# cs301_Team01_Schematic_Sensor.net
KiCad netlist of a schematic drawn in Altium Designer
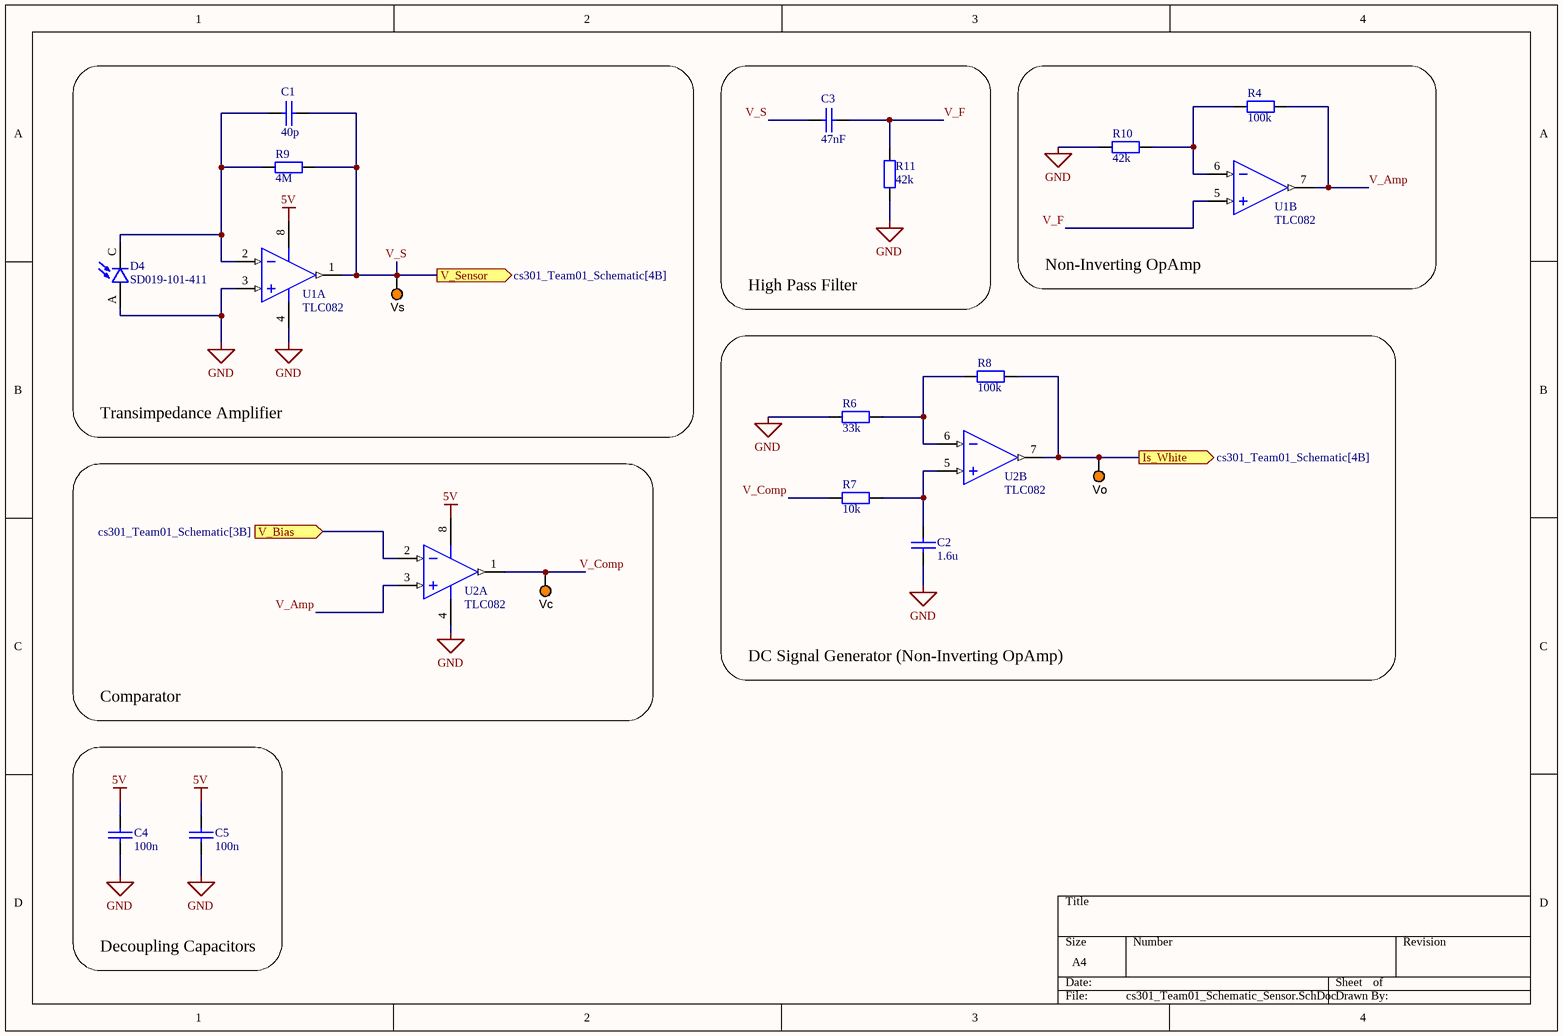
[diagram p0: cs301_Team01_Schematic_Sensor.SchDoc]

(export (version "E")
  (design (tool "Eeschema 10.0.6"))
  (components
    (comp (ref "C1")
      (value "40p")
      (footprint "0805 CAP")
      (description "SMT ceramic capacitor 0805 size")
      (libsource (lib "EE209_Library") (part "CerCap_SMT_0805"))
    )
    (comp (ref "C2")
      (value "1.6u")
      (footprint "0805 CAP")
      (description "SMT ceramic capacitor 0805 size")
      (libsource (lib "EE209_Library") (part "CerCap_SMT_0805"))
    )
    (comp (ref "C3")
      (value "47nF")
      (footprint "0805 CAP")
      (description "SMT ceramic capacitor 0805 size")
      (libsource (lib "EE209_Library") (part "CerCap_SMT_0805"))
    )
    (comp (ref "C4")
      (value "100n")
      (footprint "0805 CAP")
      (description "SMT ceramic capacitor 0805 size")
      (libsource (lib "EE209_Library") (part "CerCap_SMT_0805"))
    )
    (comp (ref "C5")
      (value "100n")
      (footprint "0805 CAP")
      (description "SMT ceramic capacitor 0805 size")
      (libsource (lib "EE209_Library") (part "CerCap_SMT_0805"))
    )
    (comp (ref "D4")
      (value "SD019-101-411")
      (footprint "XDCR_TEMD7000X01")
      (description "Photodiode SD019-101-411")
      (fields (field (name "MF") "Vishay Semiconductor") (field (name "MP") "TEMD7000X01"))
      (libsource (lib "TEMD7000X01") (part "TEMD7000X01"))
    )
    (comp (ref "R4")
      (value "100k")
      (footprint "0805 RES")
      (description "0805 resistor")
      (fields (field (name "PUBLISHER") "Altium Limited"))
      (libsource (lib "") (part "Res_SMT_0805_2"))
    )
    (comp (ref "R6")
      (value "33k")
      (footprint "0805 RES")
      (description "0805 resistor")
      (fields (field (name "PUBLISHER") "Altium Limited"))
      (libsource (lib "") (part "Res_SMT_0805_1"))
    )
    (comp (ref "R7")
      (value "10k")
      (footprint "0805 RES")
      (description "0805 resistor")
      (fields (field (name "PUBLISHER") "Altium Limited"))
      (libsource (lib "") (part "Res_SMT_0805_1"))
    )
    (comp (ref "R8")
      (value "100k")
      (footprint "0805 RES")
      (description "0805 resistor")
      (fields (field (name "PUBLISHER") "Altium Limited"))
      (libsource (lib "") (part "Res_SMT_0805_1"))
    )
    (comp (ref "R9")
      (value "4M")
      (footprint "0805 RES")
      (description "0805 resistor")
      (fields (field (name "PUBLISHER") "Altium Limited"))
      (libsource (lib "") (part "Res_SMT_0805_2"))
    )
    (comp (ref "R10")
      (value "42k")
      (footprint "0805 RES")
      (description "0805 resistor")
      (fields (field (name "PUBLISHER") "Altium Limited"))
      (libsource (lib "") (part "Res_SMT_0805_2"))
    )
    (comp (ref "R11")
      (value "42k")
      (footprint "0805 RES")
      (description "0805 resistor")
      (fields (field (name "PUBLISHER") "Altium Limited"))
      (libsource (lib "EE209_Library") (part "Res_SMT_0805"))
    )
    (comp (ref "U1")
      (value "TLC082")
      (footprint "SO - 8")
      (description "IC OPAMP GP 10MHZ 8SOIC")
      (fields
        (field (name "MANUFACTURER") "Texas Instruments")
        (field (name "MANUFACTURER PART NUMBER") "TLC082CDR")
      )
      (libsource (lib "EE209_Library") (part "TLC082_SMT_SOIC8"))
    )
    (comp (ref "U2")
      (value "TLC082")
      (footprint "SO - 8")
      (description "IC OPAMP GP 10MHZ 8SOIC")
      (fields
        (field (name "MANUFACTURER") "Texas Instruments")
        (field (name "MANUFACTURER PART NUMBER") "TLC082CDR")
      )
      (libsource (lib "EE209_Library") (part "TLC082_SMT_SOIC8"))
    )
    (comp (ref "Vc")
      (value "5003")
      (footprint "TP_TH")
      (description "Test Point, Orange, 1-Pin THD, RoHS")
      (libsource (lib "EE209_Library") (part "TestPoint"))
    )
    (comp (ref "Vo")
      (value "5003")
      (footprint "TP_TH")
      (description "Test Point, Orange, 1-Pin THD, RoHS")
      (libsource (lib "EE209_Library") (part "TestPoint"))
    )
    (comp (ref "Vs")
      (value "5003")
      (footprint "TP_TH")
      (description "Test Point, Orange, 1-Pin THD, RoHS")
      (libsource (lib "EE209_Library") (part "TestPoint"))
    )
  )
  (nets
    (net (code "1") (name "/Is_White") (class "Default")
      (node (ref "R8") (pin "1") (pinfunction "1_1") (pintype "passive"))
      (node (ref "U2") (pin "7") (pinfunction "VOUTA_7") (pintype "output"))
      (node (ref "Vo") (pin "1") (pinfunction "1_1") (pintype "passive"))
    )
    (net (code "2") (name "/V_Amp") (class "Default")
      (node (ref "R4") (pin "2") (pinfunction "2_2") (pintype "passive"))
      (node (ref "U1") (pin "7") (pinfunction "VOUTA_7") (pintype "output"))
      (node (ref "U2") (pin "3") (pinfunction "VINA+_3") (pintype "input"))
    )
    (net (code "3") (name "/V_Bias") (class "Default")
      (node (ref "U2") (pin "2") (pinfunction "VINA-_2") (pintype "input"))
    )
    (net (code "4") (name "/V_Comp") (class "Default")
      (node (ref "R7") (pin "2") (pinfunction "2_2") (pintype "passive"))
      (node (ref "U2") (pin "1") (pinfunction "VOUTA_1") (pintype "output"))
      (node (ref "Vc") (pin "1") (pinfunction "1_1") (pintype "passive"))
    )
    (net (code "5") (name "/V_F") (class "Default")
      (node (ref "C3") (pin "2") (pinfunction "2_2") (pintype "passive"))
      (node (ref "R11") (pin "2") (pinfunction "2_2") (pintype "passive"))
      (node (ref "U1") (pin "5") (pinfunction "VINA+_5") (pintype "input"))
    )
    (net (code "6") (name "/V_S") (class "Default")
      (node (ref "C1") (pin "2") (pinfunction "2_2") (pintype "passive"))
      (node (ref "C3") (pin "1") (pinfunction "1_1") (pintype "passive"))
      (node (ref "R9") (pin "2") (pinfunction "2_2") (pintype "passive"))
      (node (ref "U1") (pin "1") (pinfunction "VOUTA_1") (pintype "output"))
      (node (ref "Vs") (pin "1") (pinfunction "1_1") (pintype "passive"))
    )
    (net (code "7") (name "5V") (class "Default")
      (node (ref "C4") (pin "1") (pinfunction "1_1") (pintype "passive"))
      (node (ref "C5") (pin "1") (pinfunction "1_1") (pintype "passive"))
      (node (ref "U1") (pin "8") (pinfunction "VDD_8") (pintype "power_in"))
      (node (ref "U2") (pin "8") (pinfunction "VDD_8") (pintype "power_in"))
    )
    (net (code "8") (name "GND") (class "Default")
      (node (ref "C2") (pin "1") (pinfunction "1_1") (pintype "passive"))
      (node (ref "C4") (pin "2") (pinfunction "2_2") (pintype "passive"))
      (node (ref "C5") (pin "2") (pinfunction "2_2") (pintype "passive"))
      (node (ref "D4") (pin "A") (pinfunction "A_A") (pintype "passive"))
      (node (ref "R10") (pin "1") (pinfunction "1_1") (pintype "passive"))
      (node (ref "R11") (pin "1") (pinfunction "1_1") (pintype "passive"))
      (node (ref "R6") (pin "2") (pinfunction "2_2") (pintype "passive"))
      (node (ref "U1") (pin "3") (pinfunction "VINA+_3") (pintype "input"))
      (node (ref "U1") (pin "4") (pinfunction "VSS_4") (pintype "power_in"))
      (node (ref "U2") (pin "4") (pinfunction "VSS_4") (pintype "power_in"))
    )
    (net (code "9") (name "Net-(U1A-VINA-)") (class "Default")
      (node (ref "C1") (pin "1") (pinfunction "1_1") (pintype "passive"))
      (node (ref "D4") (pin "C") (pinfunction "C_C") (pintype "passive"))
      (node (ref "R9") (pin "1") (pinfunction "1_1") (pintype "passive"))
      (node (ref "U1") (pin "2") (pinfunction "VINA-_2") (pintype "input"))
    )
    (net (code "10") (name "Net-(U1B-VINA-)") (class "Default")
      (node (ref "R10") (pin "2") (pinfunction "2_2") (pintype "passive"))
      (node (ref "R4") (pin "1") (pinfunction "1_1") (pintype "passive"))
      (node (ref "U1") (pin "6") (pinfunction "VINA-_6") (pintype "input"))
    )
    (net (code "11") (name "Net-(U2B-VINA+)") (class "Default")
      (node (ref "C2") (pin "2") (pinfunction "2_2") (pintype "passive"))
      (node (ref "R7") (pin "1") (pinfunction "1_1") (pintype "passive"))
      (node (ref "U2") (pin "5") (pinfunction "VINA+_5") (pintype "input"))
    )
    (net (code "12") (name "Net-(U2B-VINA-)") (class "Default")
      (node (ref "R6") (pin "1") (pinfunction "1_1") (pintype "passive"))
      (node (ref "R8") (pin "2") (pinfunction "2_2") (pintype "passive"))
      (node (ref "U2") (pin "6") (pinfunction "VINA-_6") (pintype "input"))
    )
  )
)
